# inverter.net
KiCad netlist of a schematic drawn in Altium Designer
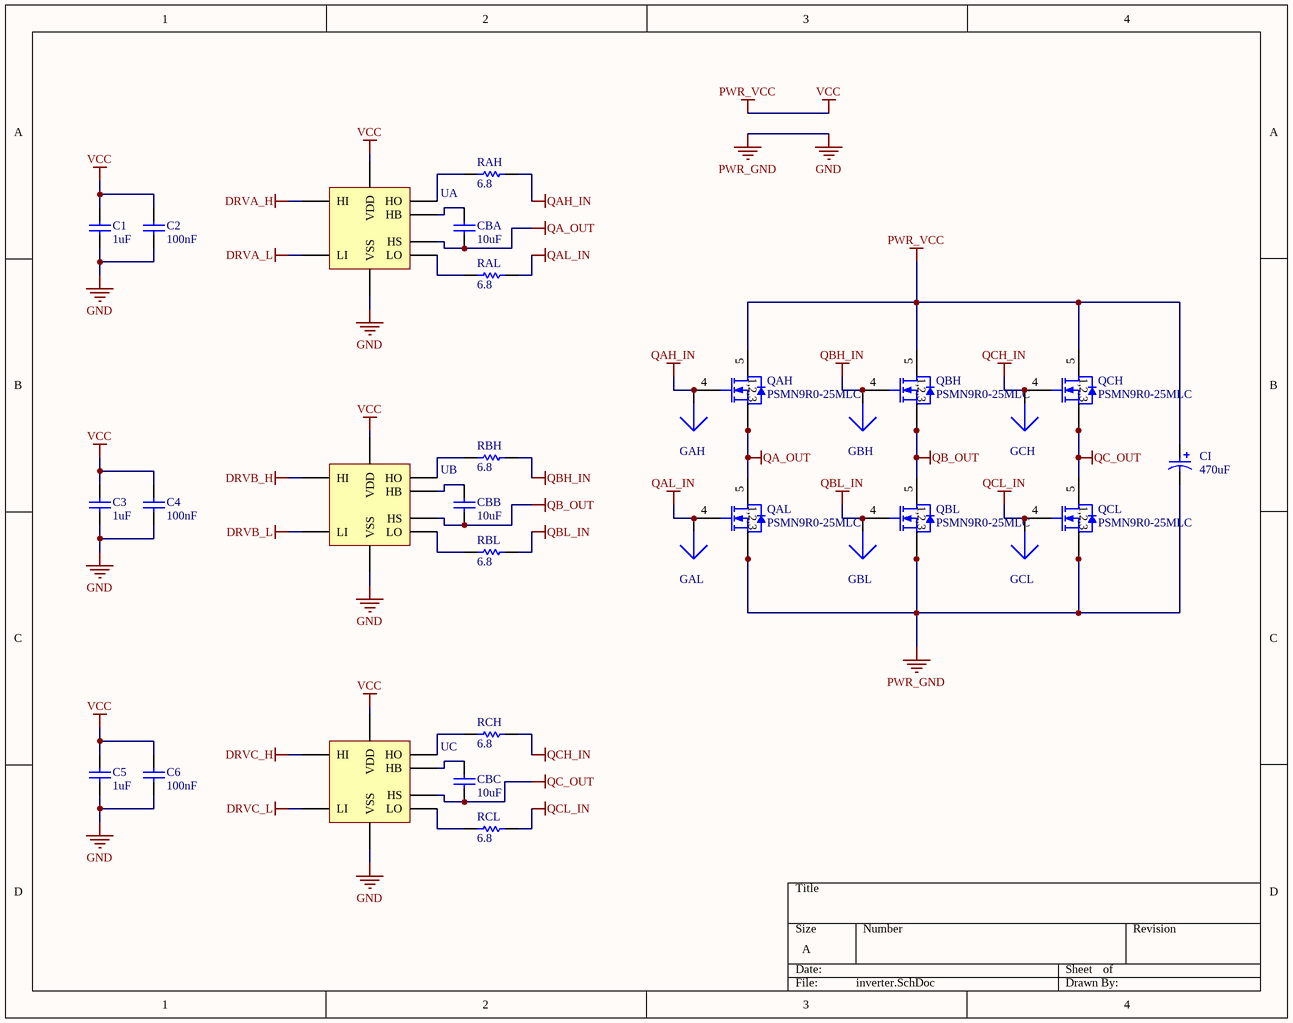
[diagram p0: inverter.SchDoc]

(export (version "E")
  (design (tool "Eeschema 10.0.6"))
  (components
    (comp (ref "C1")
      (value "1uF")
      (footprint "CAPC1608L")
      (description "CAP CER 1UF 25V 10% X5R 0603")
      (fields (field (name "MANUFACTURER PART NUMBER") "TMK107BJ105KA-T"))
      (libsource (lib "flxlib") (part "CAP-NO_POL"))
    )
    (comp (ref "C2")
      (value "100nF")
      (footprint "CAPC1608L")
      (description "CAP CER 0.1UF 50V Y5V 0603")
      (fields (field (name "MANUFACTURER PART NUMBER") "CC0603ZRY5V9BB104"))
      (libsource (lib "flxlib") (part "CAP-NO_POL"))
    )
    (comp (ref "C3")
      (value "1uF")
      (footprint "CAPC1608L")
      (description "CAP CER 1UF 25V 10% X5R 0603")
      (fields (field (name "MANUFACTURER PART NUMBER") "TMK107BJ105KA-T"))
      (libsource (lib "flxlib") (part "CAP-NO_POL"))
    )
    (comp (ref "C4")
      (value "100nF")
      (footprint "CAPC1608L")
      (description "CAP CER 0.1UF 50V Y5V 0603")
      (fields (field (name "MANUFACTURER PART NUMBER") "CC0603ZRY5V9BB104"))
      (libsource (lib "flxlib") (part "CAP-NO_POL"))
    )
    (comp (ref "C5")
      (value "1uF")
      (footprint "CAPC1608L")
      (description "CAP CER 1UF 25V 10% X5R 0603")
      (fields (field (name "MANUFACTURER PART NUMBER") "TMK107BJ105KA-T"))
      (libsource (lib "flxlib") (part "CAP-NO_POL"))
    )
    (comp (ref "C6")
      (value "100nF")
      (footprint "CAPC1608L")
      (description "CAP CER 0.1UF 50V Y5V 0603")
      (fields (field (name "MANUFACTURER PART NUMBER") "CC0603ZRY5V9BB104"))
      (libsource (lib "flxlib") (part "CAP-NO_POL"))
    )
    (comp (ref "CBA")
      (value "10uF")
      (footprint "CAPC3216L")
      (description "CAP CER 10UF 25V Y5V 1206")
      (fields (field (name "MANUFACTURER PART NUMBER") "TMK316F106ZL-T"))
      (libsource (lib "flxlib") (part "CAP-NO_POL"))
    )
    (comp (ref "CBB")
      (value "10uF")
      (footprint "CAPC3216L")
      (description "CAP CER 10UF 25V Y5V 1206")
      (fields (field (name "MANUFACTURER PART NUMBER") "TMK316F106ZL-T"))
      (libsource (lib "flxlib") (part "CAP-NO_POL"))
    )
    (comp (ref "CBC")
      (value "10uF")
      (footprint "CAPC3216L")
      (description "CAP CER 10UF 25V Y5V 1206")
      (fields (field (name "MANUFACTURER PART NUMBER") "TMK316F106ZL-T"))
      (libsource (lib "flxlib") (part "CAP-NO_POL"))
    )
    (comp (ref "CI")
      (value "470uF")
      (footprint "CAP_RADIAL-CAN_SMD_M10")
      (description "CAP ALUM 470UF 25V 20% SMD")
      (fields
        (field (name "MANUFACTURER") "Nichicon")
        (field (name "MANUFACTURER PART NUMBER") "UCW1E471MNL1GS")
      )
      (libsource (lib "flxlib") (part "CAP-POL"))
    )
    (comp (ref "GAH")
      (value "TESTPOINT-ARROW-BLUE")
      (footprint "TESTP_PAD_.75mm")
      (description "Round Test Point on Board")
      (libsource (lib "flxlib") (part "TESTPOINT-ARROW-BLUE"))
    )
    (comp (ref "GAL")
      (value "TESTPOINT-ARROW-BLUE")
      (footprint "TESTP_PAD_.75mm")
      (description "Round Test Point on Board")
      (libsource (lib "flxlib") (part "TESTPOINT-ARROW-BLUE"))
    )
    (comp (ref "GBH")
      (value "TESTPOINT-ARROW-BLUE")
      (footprint "TESTP_PAD_.75mm")
      (description "Round Test Point on Board")
      (libsource (lib "flxlib") (part "TESTPOINT-ARROW-BLUE"))
    )
    (comp (ref "GBL")
      (value "TESTPOINT-ARROW-BLUE")
      (footprint "TESTP_PAD_.75mm")
      (description "Round Test Point on Board")
      (libsource (lib "flxlib") (part "TESTPOINT-ARROW-BLUE"))
    )
    (comp (ref "GCH")
      (value "TESTPOINT-ARROW-BLUE")
      (footprint "TESTP_PAD_.75mm")
      (description "Round Test Point on Board")
      (libsource (lib "flxlib") (part "TESTPOINT-ARROW-BLUE"))
    )
    (comp (ref "GCL")
      (value "TESTPOINT-ARROW-BLUE")
      (footprint "TESTP_PAD_.75mm")
      (description "Round Test Point on Board")
      (libsource (lib "flxlib") (part "TESTPOINT-ARROW-BLUE"))
    )
    (comp (ref "QAH")
      (value "PSMN9R0-25MLC")
      (footprint "x-NXP_LFPAK33")
      (description "TRANSISTOR MOSFET N-CHANN 25V 8.6MOHM")
      (fields
        (field (name "MANUFACTURER") "NXP Semiconductors")
        (field (name "MANUFACTURER PART NUMBER") "PSMN9R0-25MLC,115")
      )
      (libsource (lib "flxlib") (part "MOSFET-N-SSSGD"))
    )
    (comp (ref "QAL")
      (value "PSMN9R0-25MLC")
      (footprint "x-NXP_LFPAK33")
      (description "TRANSISTOR MOSFET N-CHANN 25V 8.6MOHM")
      (fields
        (field (name "MANUFACTURER") "NXP Semiconductors")
        (field (name "MANUFACTURER PART NUMBER") "PSMN9R0-25MLC,115")
      )
      (libsource (lib "flxlib") (part "MOSFET-N-SSSGD"))
    )
    (comp (ref "QBH")
      (value "PSMN9R0-25MLC")
      (footprint "x-NXP_LFPAK33")
      (description "TRANSISTOR MOSFET N-CHANN 25V 8.6MOHM")
      (fields
        (field (name "MANUFACTURER") "NXP Semiconductors")
        (field (name "MANUFACTURER PART NUMBER") "PSMN9R0-25MLC,115")
      )
      (libsource (lib "flxlib") (part "MOSFET-N-SSSGD"))
    )
    (comp (ref "QBL")
      (value "PSMN9R0-25MLC")
      (footprint "x-NXP_LFPAK33")
      (description "TRANSISTOR MOSFET N-CHANN 25V 8.6MOHM")
      (fields
        (field (name "MANUFACTURER") "NXP Semiconductors")
        (field (name "MANUFACTURER PART NUMBER") "PSMN9R0-25MLC,115")
      )
      (libsource (lib "flxlib") (part "MOSFET-N-SSSGD"))
    )
    (comp (ref "QCH")
      (value "PSMN9R0-25MLC")
      (footprint "x-NXP_LFPAK33")
      (description "TRANSISTOR MOSFET N-CHANN 25V 8.6MOHM")
      (fields
        (field (name "MANUFACTURER") "NXP Semiconductors")
        (field (name "MANUFACTURER PART NUMBER") "PSMN9R0-25MLC,115")
      )
      (libsource (lib "flxlib") (part "MOSFET-N-SSSGD"))
    )
    (comp (ref "QCL")
      (value "PSMN9R0-25MLC")
      (footprint "x-NXP_LFPAK33")
      (description "TRANSISTOR MOSFET N-CHANN 25V 8.6MOHM")
      (fields
        (field (name "MANUFACTURER") "NXP Semiconductors")
        (field (name "MANUFACTURER PART NUMBER") "PSMN9R0-25MLC,115")
      )
      (libsource (lib "flxlib") (part "MOSFET-N-SSSGD"))
    )
    (comp (ref "RAH")
      (value "6.8")
      (footprint "RESC1608L")
      (description "RES 6.8 OHM 1/10W 1% 0603")
      (fields
        (field (name "MANUFACTURER") "Stackpole Electronics Inc")
        (field (name "MANUFACTURER PART NUMBER") "RMCF0603FT6R80")
      )
      (libsource (lib "flxlib") (part "RES"))
    )
    (comp (ref "RAL")
      (value "6.8")
      (footprint "RESC1608L")
      (description "RES 6.8 OHM 1/10W 1% 0603")
      (fields
        (field (name "MANUFACTURER") "Stackpole Electronics Inc")
        (field (name "MANUFACTURER PART NUMBER") "RMCF0603FT6R80")
      )
      (libsource (lib "flxlib") (part "RES"))
    )
    (comp (ref "RBH")
      (value "6.8")
      (footprint "RESC1608L")
      (description "RES 6.8 OHM 1/10W 1% 0603")
      (fields
        (field (name "MANUFACTURER") "Stackpole Electronics Inc")
        (field (name "MANUFACTURER PART NUMBER") "RMCF0603FT6R80")
      )
      (libsource (lib "flxlib") (part "RES"))
    )
    (comp (ref "RBL")
      (value "6.8")
      (footprint "RESC1608L")
      (description "RES 6.8 OHM 1/10W 1% 0603")
      (fields
        (field (name "MANUFACTURER") "Stackpole Electronics Inc")
        (field (name "MANUFACTURER PART NUMBER") "RMCF0603FT6R80")
      )
      (libsource (lib "flxlib") (part "RES"))
    )
    (comp (ref "RCH")
      (value "6.8")
      (footprint "RESC1608L")
      (description "RES 6.8 OHM 1/10W 1% 0603")
      (fields
        (field (name "MANUFACTURER") "Stackpole Electronics Inc")
        (field (name "MANUFACTURER PART NUMBER") "RMCF0603FT6R80")
      )
      (libsource (lib "flxlib") (part "RES"))
    )
    (comp (ref "RCL")
      (value "6.8")
      (footprint "RESC1608L")
      (description "RES 6.8 OHM 1/10W 1% 0603")
      (fields
        (field (name "MANUFACTURER") "Stackpole Electronics Inc")
        (field (name "MANUFACTURER PART NUMBER") "RMCF0603FT6R80")
      )
      (libsource (lib "flxlib") (part "RES"))
    )
    (comp (ref "UA")
      (value "UCC27201A")
      (footprint "x-TI_S-PVSON-N9")
      (description "IC DVR HIGH/LOW SIDE 3A 9SON")
      (fields
        (field (name "MANUFACTURER") "Texas Instruments")
        (field (name "MANUFACTURER PART NUMBER") "UCC27201ADRCT")
      )
      (libsource (lib "flxlib") (part "UCC27201A"))
    )
    (comp (ref "UB")
      (value "UCC27201A")
      (footprint "x-TI_S-PVSON-N9")
      (description "IC DVR HIGH/LOW SIDE 3A 9SON")
      (fields
        (field (name "MANUFACTURER") "Texas Instruments")
        (field (name "MANUFACTURER PART NUMBER") "UCC27201ADRCT")
      )
      (libsource (lib "flxlib") (part "UCC27201A"))
    )
    (comp (ref "UC")
      (value "UCC27201A")
      (footprint "x-TI_S-PVSON-N9")
      (description "IC DVR HIGH/LOW SIDE 3A 9SON")
      (fields
        (field (name "MANUFACTURER") "Texas Instruments")
        (field (name "MANUFACTURER PART NUMBER") "UCC27201ADRCT")
      )
      (libsource (lib "flxlib") (part "UCC27201A"))
    )
  )
  (nets
    (net (code "1") (name "DRVA_H") (class "Default")
      (node (ref "UA") (pin "6") (pinfunction "HI_6") (pintype "passive"))
    )
    (net (code "2") (name "DRVA_L") (class "Default")
      (node (ref "UA") (pin "7") (pinfunction "LI_7") (pintype "passive"))
    )
    (net (code "3") (name "DRVB_H") (class "Default")
      (node (ref "UB") (pin "6") (pinfunction "HI_6") (pintype "passive"))
    )
    (net (code "4") (name "DRVB_L") (class "Default")
      (node (ref "UB") (pin "7") (pinfunction "LI_7") (pintype "passive"))
    )
    (net (code "5") (name "DRVC_H") (class "Default")
      (node (ref "UC") (pin "6") (pinfunction "HI_6") (pintype "passive"))
    )
    (net (code "6") (name "DRVC_L") (class "Default")
      (node (ref "UC") (pin "7") (pinfunction "LI_7") (pintype "passive"))
    )
    (net (code "7") (name "GND") (class "Default")
      (node (ref "C1") (pin "2") (pinfunction "2_2") (pintype "passive"))
      (node (ref "C2") (pin "2") (pinfunction "2_2") (pintype "passive"))
      (node (ref "C3") (pin "2") (pinfunction "2_2") (pintype "passive"))
      (node (ref "C4") (pin "2") (pinfunction "2_2") (pintype "passive"))
      (node (ref "C5") (pin "2") (pinfunction "2_2") (pintype "passive"))
      (node (ref "C6") (pin "2") (pinfunction "2_2") (pintype "passive"))
      (node (ref "CI") (pin "2") (pinfunction "2_2") (pintype "passive"))
      (node (ref "QAL") (pin "1") (pinfunction "S_1") (pintype "passive"))
      (node (ref "QAL") (pin "2") (pinfunction "S_2") (pintype "passive"))
      (node (ref "QAL") (pin "3") (pinfunction "S_3") (pintype "passive"))
      (node (ref "QBL") (pin "1") (pinfunction "S_1") (pintype "passive"))
      (node (ref "QBL") (pin "2") (pinfunction "S_2") (pintype "passive"))
      (node (ref "QBL") (pin "3") (pinfunction "S_3") (pintype "passive"))
      (node (ref "QCL") (pin "1") (pinfunction "S_1") (pintype "passive"))
      (node (ref "QCL") (pin "2") (pinfunction "S_2") (pintype "passive"))
      (node (ref "QCL") (pin "3") (pinfunction "S_3") (pintype "passive"))
      (node (ref "UA") (pin "8") (pinfunction "VSS_8") (pintype "passive"))
      (node (ref "UB") (pin "8") (pinfunction "VSS_8") (pintype "passive"))
      (node (ref "UC") (pin "8") (pinfunction "VSS_8") (pintype "passive"))
    )
    (net (code "8") (name "Net-(UA-HB)") (class "Default")
      (node (ref "CBA") (pin "1") (pinfunction "1_1") (pintype "passive"))
      (node (ref "UA") (pin "2") (pinfunction "HB_2") (pintype "passive"))
    )
    (net (code "9") (name "Net-(UA-HO)") (class "Default")
      (node (ref "RAH") (pin "2") (pinfunction "2_2") (pintype "passive"))
      (node (ref "UA") (pin "3") (pinfunction "HO_3") (pintype "passive"))
    )
    (net (code "10") (name "Net-(UA-LO)") (class "Default")
      (node (ref "RAL") (pin "2") (pinfunction "2_2") (pintype "passive"))
      (node (ref "UA") (pin "9") (pinfunction "LO_9") (pintype "passive"))
    )
    (net (code "11") (name "Net-(UB-HB)") (class "Default")
      (node (ref "CBB") (pin "1") (pinfunction "1_1") (pintype "passive"))
      (node (ref "UB") (pin "2") (pinfunction "HB_2") (pintype "passive"))
    )
    (net (code "12") (name "Net-(UB-HO)") (class "Default")
      (node (ref "RBH") (pin "2") (pinfunction "2_2") (pintype "passive"))
      (node (ref "UB") (pin "3") (pinfunction "HO_3") (pintype "passive"))
    )
    (net (code "13") (name "Net-(UB-LO)") (class "Default")
      (node (ref "RBL") (pin "2") (pinfunction "2_2") (pintype "passive"))
      (node (ref "UB") (pin "9") (pinfunction "LO_9") (pintype "passive"))
    )
    (net (code "14") (name "Net-(UC-HB)") (class "Default")
      (node (ref "CBC") (pin "1") (pinfunction "1_1") (pintype "passive"))
      (node (ref "UC") (pin "2") (pinfunction "HB_2") (pintype "passive"))
    )
    (net (code "15") (name "Net-(UC-HO)") (class "Default")
      (node (ref "RCH") (pin "2") (pinfunction "2_2") (pintype "passive"))
      (node (ref "UC") (pin "3") (pinfunction "HO_3") (pintype "passive"))
    )
    (net (code "16") (name "Net-(UC-LO)") (class "Default")
      (node (ref "RCL") (pin "2") (pinfunction "2_2") (pintype "passive"))
      (node (ref "UC") (pin "9") (pinfunction "LO_9") (pintype "passive"))
    )
    (net (code "17") (name "PWR_VCC") (class "Default")
      (node (ref "C1") (pin "1") (pinfunction "1_1") (pintype "passive"))
      (node (ref "C2") (pin "1") (pinfunction "1_1") (pintype "passive"))
      (node (ref "C3") (pin "1") (pinfunction "1_1") (pintype "passive"))
      (node (ref "C4") (pin "1") (pinfunction "1_1") (pintype "passive"))
      (node (ref "C5") (pin "1") (pinfunction "1_1") (pintype "passive"))
      (node (ref "C6") (pin "1") (pinfunction "1_1") (pintype "passive"))
      (node (ref "CI") (pin "1") (pinfunction "1_1") (pintype "passive"))
      (node (ref "QAH") (pin "5") (pinfunction "D_5") (pintype "passive"))
      (node (ref "QBH") (pin "5") (pinfunction "D_5") (pintype "passive"))
      (node (ref "QCH") (pin "5") (pinfunction "D_5") (pintype "passive"))
      (node (ref "UA") (pin "1") (pinfunction "VDD_1") (pintype "passive"))
      (node (ref "UB") (pin "1") (pinfunction "VDD_1") (pintype "passive"))
      (node (ref "UC") (pin "1") (pinfunction "VDD_1") (pintype "passive"))
    )
    (net (code "18") (name "QAH_IN") (class "Default")
      (node (ref "GAH") (pin "1") (pinfunction "1_1") (pintype "passive"))
      (node (ref "QAH") (pin "4") (pinfunction "G_4") (pintype "passive"))
      (node (ref "RAH") (pin "1") (pinfunction "1_1") (pintype "passive"))
    )
    (net (code "19") (name "QAL_IN") (class "Default")
      (node (ref "GAL") (pin "1") (pinfunction "1_1") (pintype "passive"))
      (node (ref "QAL") (pin "4") (pinfunction "G_4") (pintype "passive"))
      (node (ref "RAL") (pin "1") (pinfunction "1_1") (pintype "passive"))
    )
    (net (code "20") (name "QA_OUT") (class "Default")
      (node (ref "CBA") (pin "2") (pinfunction "2_2") (pintype "passive"))
      (node (ref "QAH") (pin "1") (pinfunction "S_1") (pintype "passive"))
      (node (ref "QAH") (pin "2") (pinfunction "S_2") (pintype "passive"))
      (node (ref "QAH") (pin "3") (pinfunction "S_3") (pintype "passive"))
      (node (ref "QAL") (pin "5") (pinfunction "D_5") (pintype "passive"))
      (node (ref "UA") (pin "4") (pinfunction "HS_4") (pintype "passive"))
    )
    (net (code "21") (name "QBH_IN") (class "Default")
      (node (ref "GBH") (pin "1") (pinfunction "1_1") (pintype "passive"))
      (node (ref "QBH") (pin "4") (pinfunction "G_4") (pintype "passive"))
      (node (ref "RBH") (pin "1") (pinfunction "1_1") (pintype "passive"))
    )
    (net (code "22") (name "QBL_IN") (class "Default")
      (node (ref "GBL") (pin "1") (pinfunction "1_1") (pintype "passive"))
      (node (ref "QBL") (pin "4") (pinfunction "G_4") (pintype "passive"))
      (node (ref "RBL") (pin "1") (pinfunction "1_1") (pintype "passive"))
    )
    (net (code "23") (name "QB_OUT") (class "Default")
      (node (ref "CBB") (pin "2") (pinfunction "2_2") (pintype "passive"))
      (node (ref "QBH") (pin "1") (pinfunction "S_1") (pintype "passive"))
      (node (ref "QBH") (pin "2") (pinfunction "S_2") (pintype "passive"))
      (node (ref "QBH") (pin "3") (pinfunction "S_3") (pintype "passive"))
      (node (ref "QBL") (pin "5") (pinfunction "D_5") (pintype "passive"))
      (node (ref "UB") (pin "4") (pinfunction "HS_4") (pintype "passive"))
    )
    (net (code "24") (name "QCH_IN") (class "Default")
      (node (ref "GCH") (pin "1") (pinfunction "1_1") (pintype "passive"))
      (node (ref "QCH") (pin "4") (pinfunction "G_4") (pintype "passive"))
      (node (ref "RCH") (pin "1") (pinfunction "1_1") (pintype "passive"))
    )
    (net (code "25") (name "QCL_IN") (class "Default")
      (node (ref "GCL") (pin "1") (pinfunction "1_1") (pintype "passive"))
      (node (ref "QCL") (pin "4") (pinfunction "G_4") (pintype "passive"))
      (node (ref "RCL") (pin "1") (pinfunction "1_1") (pintype "passive"))
    )
    (net (code "26") (name "QC_OUT") (class "Default")
      (node (ref "CBC") (pin "2") (pinfunction "2_2") (pintype "passive"))
      (node (ref "QCH") (pin "1") (pinfunction "S_1") (pintype "passive"))
      (node (ref "QCH") (pin "2") (pinfunction "S_2") (pintype "passive"))
      (node (ref "QCH") (pin "3") (pinfunction "S_3") (pintype "passive"))
      (node (ref "QCL") (pin "5") (pinfunction "D_5") (pintype "passive"))
      (node (ref "UC") (pin "4") (pinfunction "HS_4") (pintype "passive"))
    )
  )
)
